# mapleCUx_large_067.net
KiCad netlist of a schematic drawn in EAGLE
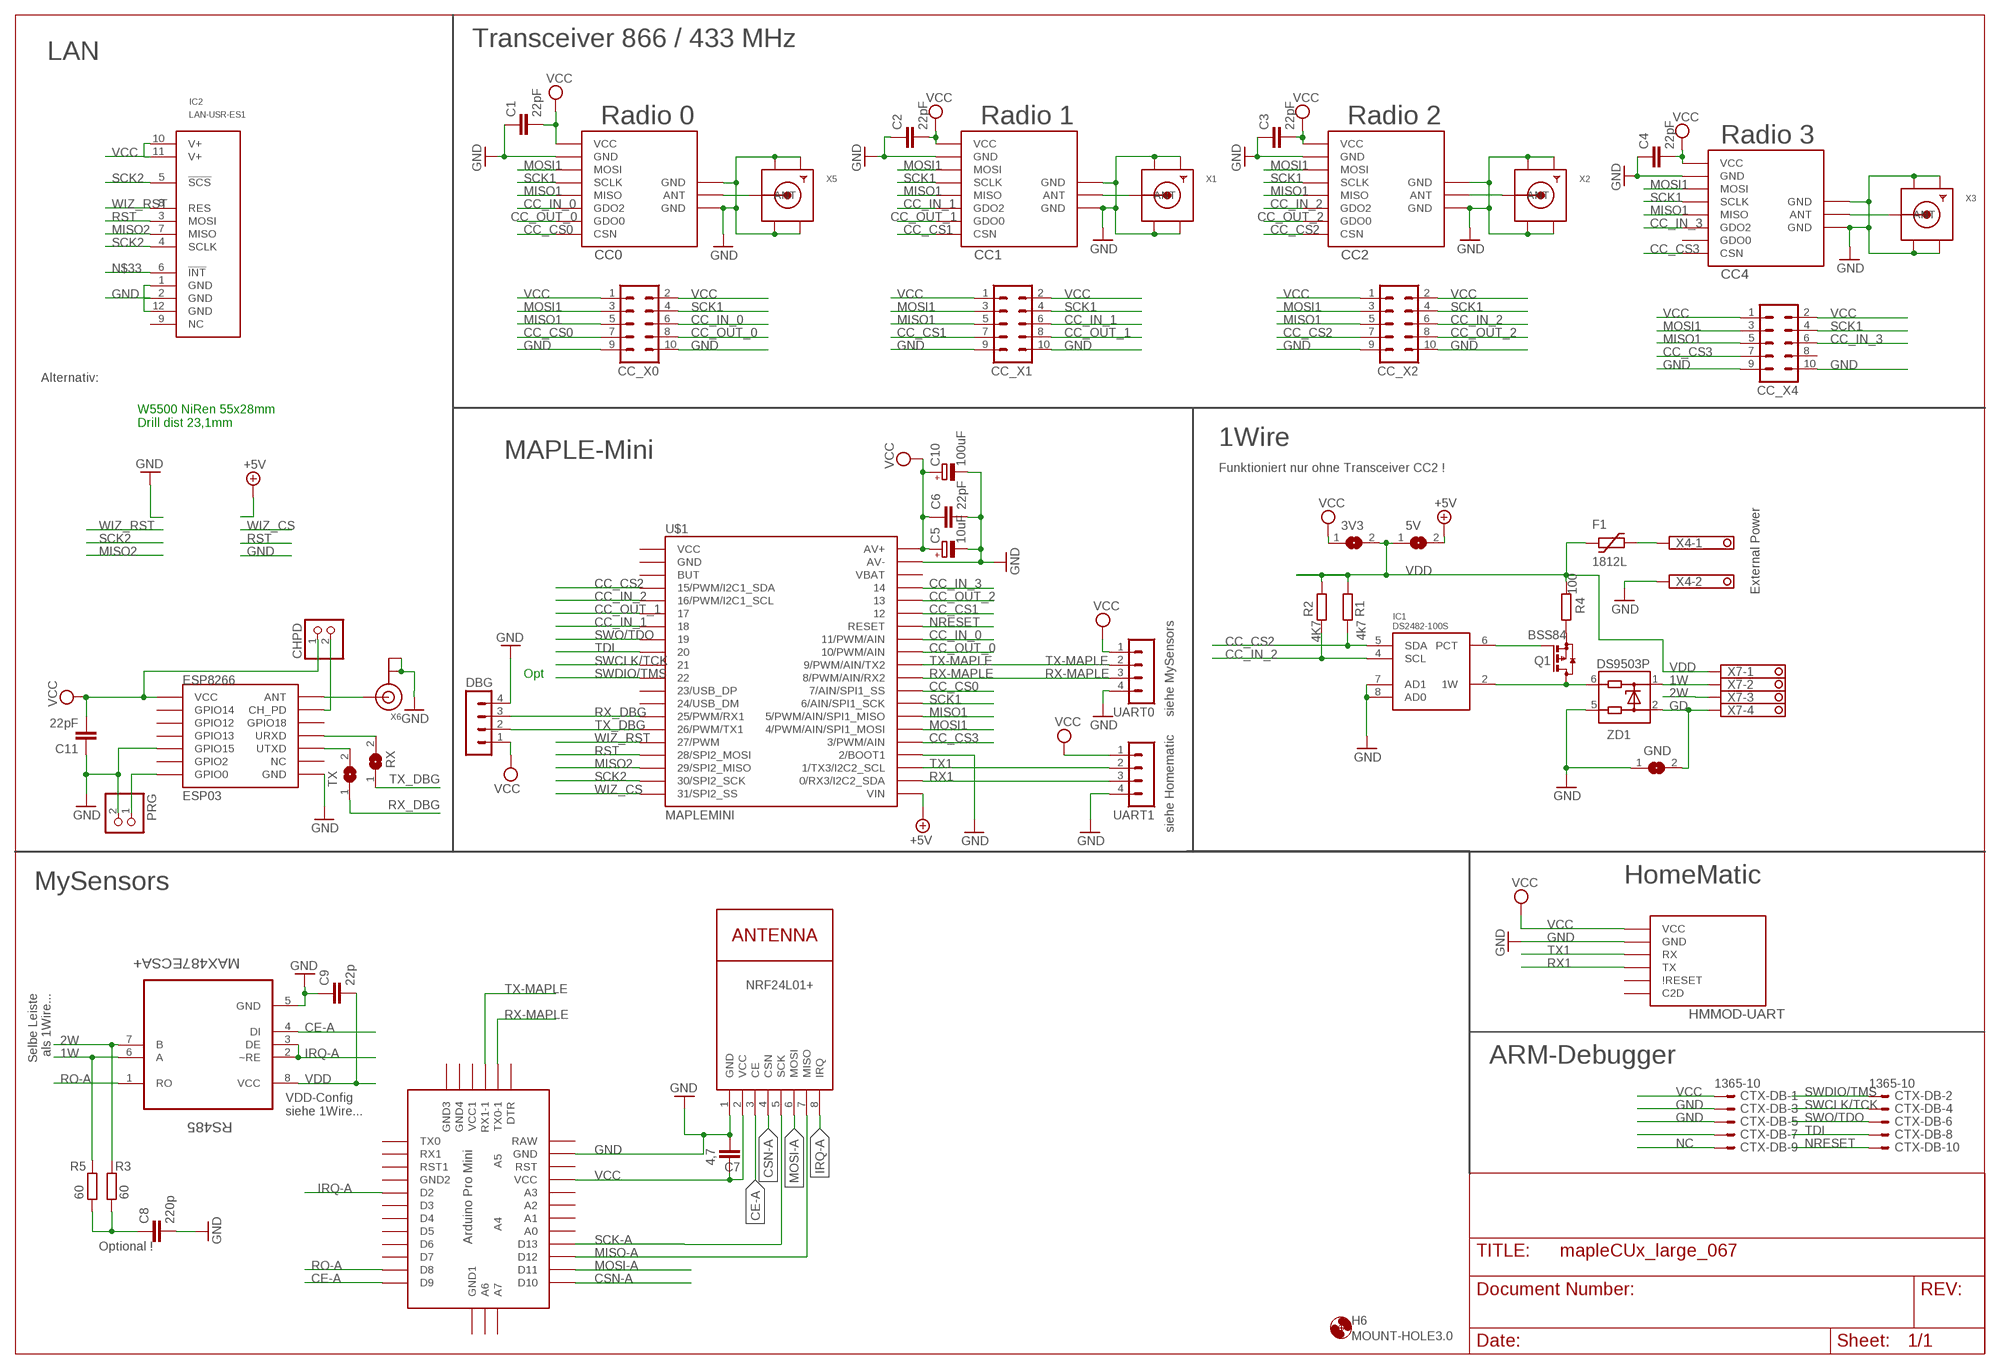
[diagram p0: schematic, sheet 1]

(export (version "E")
  (design (tool "Eeschema 10.0.6"))
  (components
    (comp (ref "3V3") (value "SJ") (footprint "eagle-import:SJ") (libsource (lib "eagle-import") (part "SJ")))
    (comp (ref "5V") (value "SJ") (footprint "eagle-import:SJ") (libsource (lib "eagle-import") (part "SJ")))
    (comp (ref "C1")
      (value "22pF")
      (footprint "eagle-import:C0805")
      (libsource (lib "eagle-import") (part "C-EUC0805"))
    )
    (comp (ref "C2")
      (value "22pF")
      (footprint "eagle-import:C0805")
      (libsource (lib "eagle-import") (part "C-EUC0805"))
    )
    (comp (ref "C3")
      (value "22pF")
      (footprint "eagle-import:C0805")
      (libsource (lib "eagle-import") (part "C-EUC0805"))
    )
    (comp (ref "C4")
      (value "22pF")
      (footprint "eagle-import:C0805")
      (libsource (lib "eagle-import") (part "C-EUC0805"))
    )
    (comp (ref "C5")
      (value "10uF")
      (footprint "eagle-import:R_2012-12W")
      (libsource (lib "eagle-import") (part "CPOL-EUR/2012-12W"))
    )
    (comp (ref "C6")
      (value "22pF")
      (footprint "eagle-import:C0805")
      (libsource (lib "eagle-import") (part "C-EUC0805"))
    )
    (comp (ref "C7")
      (value "4,7")
      (footprint "eagle-import:C1210")
      (libsource (lib "eagle-import") (part "C-EUC1210"))
    )
    (comp (ref "C8")
      (value "220p")
      (footprint "eagle-import:C0805")
      (libsource (lib "eagle-import") (part "C-EUC0805"))
    )
    (comp (ref "C9")
      (value "22p")
      (footprint "eagle-import:C0805")
      (libsource (lib "eagle-import") (part "C-EUC0805"))
    )
    (comp (ref "C10")
      (value "100uF")
      (footprint "eagle-import:E5-8,5")
      (libsource (lib "eagle-import") (part "CPOL-EUE5-8.5"))
    )
    (comp (ref "C11")
      (value "22pF")
      (footprint "eagle-import:C0805")
      (libsource (lib "eagle-import") (part "C-EUC0805"))
    )
    (comp (ref "CC0")
      (value "CC1101")
      (footprint "eagle-import:CC1101_MODULE1_SMD")
      (libsource (lib "eagle-import") (part "CC1101_MODULE1SMD"))
    )
    (comp (ref "CC1")
      (value "CC1101_MODULE1SMD")
      (footprint "eagle-import:CC1101_MODULE1_SMD")
      (libsource (lib "eagle-import") (part "CC1101_MODULE1SMD"))
    )
    (comp (ref "CC2")
      (value "CC1101_MODULE1SMD")
      (footprint "eagle-import:CC1101_MODULE1_SMD")
      (libsource (lib "eagle-import") (part "CC1101_MODULE1SMD"))
    )
    (comp (ref "CC4")
      (value "CC1101_MODULE1SMD")
      (footprint "eagle-import:CC1101_MODULE1_SMD")
      (libsource (lib "eagle-import") (part "CC1101_MODULE1SMD"))
    )
    (comp (ref "CC_X0")
      (value "MA05-2")
      (footprint "eagle-import:MA05-2")
      (libsource (lib "eagle-import") (part "MA05-2"))
    )
    (comp (ref "CC_X1")
      (value "MA05-2")
      (footprint "eagle-import:MA05-2")
      (libsource (lib "eagle-import") (part "MA05-2"))
    )
    (comp (ref "CC_X2")
      (value "MA05-2")
      (footprint "eagle-import:MA05-2")
      (libsource (lib "eagle-import") (part "MA05-2"))
    )
    (comp (ref "CC_X4")
      (value "MA05-2")
      (footprint "eagle-import:MA05-2")
      (libsource (lib "eagle-import") (part "MA05-2"))
    )
    (comp (ref "CHPD")
      (value "PINHD-1X2")
      (footprint "eagle-import:1X02")
      (libsource (lib "eagle-import") (part "PINHD-1X2"))
    )
    (comp (ref "CTX-DB")
      (value "1365-10")
      (footprint "eagle-import:1365-10")
      (libsource (lib "eagle-import") (part "1365-10"))
    )
    (comp (ref "DBG")
      (value "MA04-1")
      (footprint "eagle-import:MA04-1")
      (libsource (lib "eagle-import") (part "MA04-1"))
    )
    (comp (ref "ESP8266")
      (value "ESP03")
      (footprint "eagle-import:ESP03")
      (libsource (lib "eagle-import") (part "ESP03"))
    )
    (comp (ref "F1")
      (value "1812L")
      (footprint "eagle-import:1812L")
      (libsource (lib "eagle-import") (part "1812L"))
    )
    (comp (ref "GND") (value "SJ") (footprint "eagle-import:SJ") (libsource (lib "eagle-import") (part "SJ")))
    (comp (ref "H6")
      (value "MOUNT-HOLE3.0")
      (footprint "eagle-import:3,0")
      (libsource (lib "eagle-import") (part "MOUNT-HOLE3.0"))
    )
    (comp (ref "HMMOD-UART")
      (value "HM-MOD-UARTDIL")
      (footprint "eagle-import:HM-MOD-UART-DIL")
      (libsource (lib "eagle-import") (part "HM-MOD-UARTDIL"))
    )
    (comp (ref "IC1")
      (value "DS2482-100S")
      (footprint "eagle-import:SO08")
      (libsource (lib "eagle-import") (part "DS2482-100S"))
    )
    (comp (ref "IC2")
      (value "LAN-USR-ES1")
      (footprint "eagle-import:USR-ES1")
      (libsource (lib "eagle-import") (part "LAN-USR-ES1"))
    )
    (comp (ref "NRF24L01+")
      (value "NRF24L01+")
      (footprint "eagle-import:WIRELESS-NRF24L01")
      (libsource (lib "eagle-import") (part "WIRELESS-NRF24L01"))
    )
    (comp (ref "PRG")
      (value "PINHD-1X2")
      (footprint "eagle-import:1X02")
      (libsource (lib "eagle-import") (part "PINHD-1X2"))
    )
    (comp (ref "Q1")
      (value "BSS84")
      (footprint "eagle-import:SOT23")
      (libsource (lib "eagle-import") (part "BSS84"))
    )
    (comp (ref "R1")
      (value "4k7")
      (footprint "eagle-import:R0805")
      (libsource (lib "eagle-import") (part "R-EU_R0805"))
    )
    (comp (ref "R2")
      (value "4K7")
      (footprint "eagle-import:R0805")
      (libsource (lib "eagle-import") (part "R-EU_R0805"))
    )
    (comp (ref "R3")
      (value "60")
      (footprint "eagle-import:R0805")
      (libsource (lib "eagle-import") (part "R-EU_R0805"))
    )
    (comp (ref "R4")
      (value "100")
      (footprint "eagle-import:R0805")
      (libsource (lib "eagle-import") (part "R-EU_R0805"))
    )
    (comp (ref "R5")
      (value "60")
      (footprint "eagle-import:R0805")
      (libsource (lib "eagle-import") (part "R-EU_R0805"))
    )
    (comp (ref "RS485")
      (value "MAX487ECSA+")
      (footprint "eagle-import:SOIC127P600X175-8N")
      (libsource (lib "eagle-import") (part "MAX487ECSA+"))
    )
    (comp (ref "RX") (value "SJ") (footprint "eagle-import:SJ") (libsource (lib "eagle-import") (part "SJ")))
    (comp (ref "TX") (value "SJ") (footprint "eagle-import:SJ") (libsource (lib "eagle-import") (part "SJ")))
    (comp (ref "U$1")
      (value "MAPLEMINI")
      (footprint "eagle-import:20-DIP")
      (libsource (lib "eagle-import") (part "MAPLEMINI"))
    )
    (comp (ref "U$2")
      (value "ABK-PRO-MINI")
      (footprint "eagle-import:ABK-PRO-MINI")
      (libsource (lib "eagle-import") (part "ABK-PRO-MINI"))
    )
    (comp (ref "UART0")
      (value "MA04-1")
      (footprint "eagle-import:MA04-1")
      (libsource (lib "eagle-import") (part "MA04-1"))
    )
    (comp (ref "UART1")
      (value "MA04-1")
      (footprint "eagle-import:MA04-1")
      (libsource (lib "eagle-import") (part "MA04-1"))
    )
    (comp (ref "X1")
      (value "SMACONNECTOR_EDGE_UFL")
      (footprint "eagle-import:SMA_EDGELAUNCH_UFL")
      (libsource (lib "eagle-import") (part "SMACONNECTOR_EDGE_UFL"))
    )
    (comp (ref "X2")
      (value "SMACONNECTOR_EDGE_UFL")
      (footprint "eagle-import:SMA_EDGELAUNCH_UFL")
      (libsource (lib "eagle-import") (part "SMACONNECTOR_EDGE_UFL"))
    )
    (comp (ref "X3")
      (value "SMACONNECTOR_EDGE_UFL")
      (footprint "eagle-import:SMA_EDGELAUNCH_UFL")
      (libsource (lib "eagle-import") (part "SMACONNECTOR_EDGE_UFL"))
    )
    (comp (ref "X4")
      (value "1751248")
      (footprint "eagle-import:1751248")
      (libsource (lib "eagle-import") (part "1751248"))
    )
    (comp (ref "X5")
      (value "SMACONNECTOR_EDGE_UFL")
      (footprint "eagle-import:SMA_EDGELAUNCH_UFL")
      (libsource (lib "eagle-import") (part "SMACONNECTOR_EDGE_UFL"))
    )
    (comp (ref "X6")
      (value "ANTENNA_U.FL")
      (footprint "eagle-import:U.FL")
      (libsource (lib "eagle-import") (part "ANTENNA_U.FL"))
    )
    (comp (ref "X7")
      (value "1751264")
      (footprint "eagle-import:1751264")
      (libsource (lib "eagle-import") (part "1751264"))
    )
    (comp (ref "ZD1")
      (value "DS9503P")
      (footprint "eagle-import:TSOC6")
      (libsource (lib "eagle-import") (part "DS9503P"))
    )
  )
  (nets
    (net (code "1") (name "+5V") (class "Default")
      (node (ref "5V") (pin "2") (pinfunction "2_2") (pintype "passive"))
      (node (ref "U$1") (pin "21") (pinfunction "VIN_21") (pintype "bidirectional"))
    )
    (net (code "2") (name "/1W") (class "Default")
      (node (ref "R5") (pin "2") (pinfunction "2_2") (pintype "passive"))
      (node (ref "RS485") (pin "6") (pinfunction "A_6") (pintype "bidirectional"))
      (node (ref "X7") (pin "2") (pinfunction "K_2") (pintype "passive"))
      (node (ref "ZD1") (pin "1") (pinfunction "P$1_1") (pintype "passive"))
    )
    (net (code "3") (name "/2W") (class "Default")
      (node (ref "R3") (pin "2") (pinfunction "2_2") (pintype "passive"))
      (node (ref "RS485") (pin "7") (pinfunction "B_7") (pintype "bidirectional"))
      (node (ref "X7") (pin "3") (pinfunction "K_3") (pintype "passive"))
    )
    (net (code "4") (name "/CC_CS0") (class "Default")
      (node (ref "CC0") (pin "CSN") (pinfunction "CSN_CSN") (pintype "bidirectional"))
      (node (ref "CC_X0") (pin "7") (pinfunction "7_7") (pintype "passive"))
      (node (ref "U$1") (pin "29") (pinfunction "7/AIN/SPI1_SS_29") (pintype "bidirectional"))
    )
    (net (code "5") (name "/CC_CS1") (class "Default")
      (node (ref "CC1") (pin "CSN") (pinfunction "CSN_CSN") (pintype "bidirectional"))
      (node (ref "CC_X1") (pin "7") (pinfunction "7_7") (pintype "passive"))
      (node (ref "U$1") (pin "35") (pinfunction "12_35") (pintype "bidirectional"))
    )
    (net (code "6") (name "/CC_CS2") (class "Default")
      (node (ref "CC2") (pin "CSN") (pinfunction "CSN_CSN") (pintype "bidirectional"))
      (node (ref "CC_X2") (pin "7") (pinfunction "7_7") (pintype "passive"))
      (node (ref "IC1") (pin "5") (pinfunction "SDA_5") (pintype "bidirectional"))
      (node (ref "R1") (pin "2") (pinfunction "2_2") (pintype "passive"))
      (node (ref "U$1") (pin "4") (pinfunction "15/PWM/I2C1_SDA_4") (pintype "bidirectional"))
    )
    (net (code "7") (name "/CC_CS3") (class "Default")
      (node (ref "CC4") (pin "CSN") (pinfunction "CSN_CSN") (pintype "bidirectional"))
      (node (ref "CC_X4") (pin "7") (pinfunction "7_7") (pintype "passive"))
      (node (ref "U$1") (pin "25") (pinfunction "3/PWM/AIN_25") (pintype "bidirectional"))
    )
    (net (code "8") (name "/CC_IN_0") (class "Default")
      (node (ref "CC0") (pin "GDO2") (pinfunction "GDO2_GDO2") (pintype "bidirectional"))
      (node (ref "CC_X0") (pin "6") (pinfunction "6_6") (pintype "passive"))
      (node (ref "U$1") (pin "33") (pinfunction "11/PWM/AIN_33") (pintype "bidirectional"))
    )
    (net (code "9") (name "/CC_IN_1") (class "Default")
      (node (ref "CC1") (pin "GDO2") (pinfunction "GDO2_GDO2") (pintype "bidirectional"))
      (node (ref "CC_X1") (pin "6") (pinfunction "6_6") (pintype "passive"))
      (node (ref "U$1") (pin "7") (pinfunction "18_7") (pintype "bidirectional"))
    )
    (net (code "10") (name "/CC_IN_2") (class "Default")
      (node (ref "CC2") (pin "GDO2") (pinfunction "GDO2_GDO2") (pintype "bidirectional"))
      (node (ref "CC_X2") (pin "6") (pinfunction "6_6") (pintype "passive"))
      (node (ref "IC1") (pin "4") (pinfunction "SCL_4") (pintype "input"))
      (node (ref "R2") (pin "2") (pinfunction "2_2") (pintype "passive"))
      (node (ref "U$1") (pin "5") (pinfunction "16/PWM/I2C1_SCL_5") (pintype "bidirectional"))
    )
    (net (code "11") (name "/CC_IN_3") (class "Default")
      (node (ref "CC4") (pin "GDO2") (pinfunction "GDO2_GDO2") (pintype "bidirectional"))
      (node (ref "CC_X4") (pin "6") (pinfunction "6_6") (pintype "passive"))
      (node (ref "U$1") (pin "37") (pinfunction "14_37") (pintype "bidirectional"))
    )
    (net (code "12") (name "/CC_OUT_0") (class "Default")
      (node (ref "CC0") (pin "GDO0") (pinfunction "GDO0_GDO0") (pintype "bidirectional"))
      (node (ref "CC_X0") (pin "8") (pinfunction "8_8") (pintype "passive"))
      (node (ref "U$1") (pin "32") (pinfunction "10/PWM/AIN_32") (pintype "bidirectional"))
    )
    (net (code "13") (name "/CC_OUT_1") (class "Default")
      (node (ref "CC1") (pin "GDO0") (pinfunction "GDO0_GDO0") (pintype "bidirectional"))
      (node (ref "CC_X1") (pin "8") (pinfunction "8_8") (pintype "passive"))
      (node (ref "U$1") (pin "6") (pinfunction "17_6") (pintype "bidirectional"))
    )
    (net (code "14") (name "/CC_OUT_2") (class "Default")
      (node (ref "CC2") (pin "GDO0") (pinfunction "GDO0_GDO0") (pintype "bidirectional"))
      (node (ref "CC_X2") (pin "8") (pinfunction "8_8") (pintype "passive"))
      (node (ref "U$1") (pin "36") (pinfunction "13_36") (pintype "bidirectional"))
    )
    (net (code "15") (name "/GD") (class "Default")
      (node (ref "GND") (pin "2") (pinfunction "2_2") (pintype "passive"))
      (node (ref "X7") (pin "4") (pinfunction "K_4") (pintype "passive"))
      (node (ref "ZD1") (pin "2") (pinfunction "P$2_2") (pintype "passive"))
    )
    (net (code "16") (name "/MISO-A") (class "Default")
      (node (ref "NRF24L01+") (pin "7") (pinfunction "MISO_7") (pintype "bidirectional"))
      (node (ref "U$2") (pin "D12") (pinfunction "D12_D12") (pintype "bidirectional"))
    )
    (net (code "17") (name "/MISO1") (class "Default")
      (node (ref "CC0") (pin "MISO") (pinfunction "MISO_MISO") (pintype "bidirectional"))
      (node (ref "CC1") (pin "MISO") (pinfunction "MISO_MISO") (pintype "bidirectional"))
      (node (ref "CC2") (pin "MISO") (pinfunction "MISO_MISO") (pintype "bidirectional"))
      (node (ref "CC4") (pin "MISO") (pinfunction "MISO_MISO") (pintype "bidirectional"))
      (node (ref "CC_X0") (pin "5") (pinfunction "5_5") (pintype "passive"))
      (node (ref "CC_X1") (pin "5") (pinfunction "5_5") (pintype "passive"))
      (node (ref "CC_X2") (pin "5") (pinfunction "5_5") (pintype "passive"))
      (node (ref "CC_X4") (pin "5") (pinfunction "5_5") (pintype "passive"))
      (node (ref "U$1") (pin "27") (pinfunction "5/PWM/AIN/SPI1_MISO_27") (pintype "bidirectional"))
    )
    (net (code "18") (name "/MISO2") (class "Default")
      (node (ref "IC2") (pin "7") (pinfunction "MISO_7") (pintype "bidirectional"))
      (node (ref "U$1") (pin "18") (pinfunction "29/SPI2_MISO_18") (pintype "bidirectional"))
    )
    (net (code "19") (name "/MOSI1") (class "Default")
      (node (ref "CC0") (pin "MOSI") (pinfunction "MOSI_MOSI") (pintype "bidirectional"))
      (node (ref "CC1") (pin "MOSI") (pinfunction "MOSI_MOSI") (pintype "bidirectional"))
      (node (ref "CC2") (pin "MOSI") (pinfunction "MOSI_MOSI") (pintype "bidirectional"))
      (node (ref "CC4") (pin "MOSI") (pinfunction "MOSI_MOSI") (pintype "bidirectional"))
      (node (ref "CC_X0") (pin "3") (pinfunction "3_3") (pintype "passive"))
      (node (ref "CC_X1") (pin "3") (pinfunction "3_3") (pintype "passive"))
      (node (ref "CC_X2") (pin "3") (pinfunction "3_3") (pintype "passive"))
      (node (ref "CC_X4") (pin "3") (pinfunction "3_3") (pintype "passive"))
      (node (ref "U$1") (pin "26") (pinfunction "4/PWM/AIN/SPI1_MOSI_26") (pintype "bidirectional"))
    )
    (net (code "20") (name "/N$33") (class "Default")
      (node (ref "IC2") (pin "6") (pinfunction "~{INT}_6") (pintype "output"))
    )
    (net (code "21") (name "/NC") (class "Default")
      (node (ref "CTX-DB") (pin "9") (pinfunction "S_9") (pintype "passive"))
    )
    (net (code "22") (name "/NRESET") (class "Default")
      (node (ref "CTX-DB") (pin "10") (pinfunction "S_10") (pintype "passive"))
      (node (ref "U$1") (pin "34") (pinfunction "RESET_34") (pintype "bidirectional"))
    )
    (net (code "23") (name "/RO-A") (class "Default")
      (node (ref "RS485") (pin "1") (pinfunction "RO_1") (pintype "output"))
      (node (ref "U$2") (pin "D8") (pinfunction "D8_D8") (pintype "bidirectional"))
    )
    (net (code "24") (name "/RST") (class "Default")
      (node (ref "IC2") (pin "3") (pinfunction "MOSI_3") (pintype "bidirectional"))
      (node (ref "U$1") (pin "17") (pinfunction "28/SPI2_MOSI_17") (pintype "bidirectional"))
    )
    (net (code "25") (name "/RX-MAPLE") (class "Default")
      (node (ref "U$1") (pin "30") (pinfunction "8/PWM/AIN/RX2_30") (pintype "bidirectional"))
      (node (ref "U$2") (pin "TX0-1") (pinfunction "TX0-1_TX0-1") (pintype "bidirectional"))
      (node (ref "UART0") (pin "3") (pinfunction "3_3") (pintype "passive"))
    )
    (net (code "26") (name "/RX1") (class "Default")
      (node (ref "HMMOD-UART") (pin "5") (pinfunction "TX_5") (pintype "bidirectional"))
      (node (ref "U$1") (pin "22") (pinfunction "0/RX3/I2C2_SDA_22") (pintype "bidirectional"))
      (node (ref "UART1") (pin "3") (pinfunction "3_3") (pintype "passive"))
    )
    (net (code "27") (name "/RX_DBG") (class "Default")
      (node (ref "DBG") (pin "3") (pinfunction "3_3") (pintype "passive"))
      (node (ref "TX") (pin "1") (pinfunction "1_1") (pintype "passive"))
      (node (ref "U$1") (pin "14") (pinfunction "25/PWM/RX1_14") (pintype "bidirectional"))
    )
    (net (code "28") (name "/SCK-A") (class "Default")
      (node (ref "NRF24L01+") (pin "5") (pinfunction "SCK_5") (pintype "bidirectional"))
      (node (ref "U$2") (pin "D13") (pinfunction "D13_D13") (pintype "bidirectional"))
    )
    (net (code "29") (name "/SCK1") (class "Default")
      (node (ref "CC0") (pin "SCLK") (pinfunction "SCLK_SCLK") (pintype "bidirectional"))
      (node (ref "CC1") (pin "SCLK") (pinfunction "SCLK_SCLK") (pintype "bidirectional"))
      (node (ref "CC2") (pin "SCLK") (pinfunction "SCLK_SCLK") (pintype "bidirectional"))
      (node (ref "CC4") (pin "SCLK") (pinfunction "SCLK_SCLK") (pintype "bidirectional"))
      (node (ref "CC_X0") (pin "4") (pinfunction "4_4") (pintype "passive"))
      (node (ref "CC_X1") (pin "4") (pinfunction "4_4") (pintype "passive"))
      (node (ref "CC_X2") (pin "4") (pinfunction "4_4") (pintype "passive"))
      (node (ref "CC_X4") (pin "4") (pinfunction "4_4") (pintype "passive"))
      (node (ref "U$1") (pin "28") (pinfunction "6/AIN/SPI1_SCK_28") (pintype "bidirectional"))
    )
    (net (code "30") (name "/SCK2") (class "Default")
      (node (ref "IC2") (pin "4") (pinfunction "SCLK_4") (pintype "input"))
      (node (ref "IC2") (pin "5") (pinfunction "~{SCS}_5") (pintype "input"))
      (node (ref "U$1") (pin "19") (pinfunction "30/SPI2_SCK_19") (pintype "bidirectional"))
    )
    (net (code "31") (name "/SWCLK{slash}TCK") (class "Default")
      (node (ref "CTX-DB") (pin "4") (pinfunction "S_4") (pintype "passive"))
      (node (ref "U$1") (pin "10") (pinfunction "21_10") (pintype "bidirectional"))
    )
    (net (code "32") (name "/SWDIO{slash}TMS") (class "Default")
      (node (ref "CTX-DB") (pin "2") (pinfunction "S_2") (pintype "passive"))
      (node (ref "U$1") (pin "11") (pinfunction "22_11") (pintype "bidirectional"))
    )
    (net (code "33") (name "/SWO{slash}TDO") (class "Default")
      (node (ref "CTX-DB") (pin "6") (pinfunction "S_6") (pintype "passive"))
      (node (ref "U$1") (pin "8") (pinfunction "19_8") (pintype "bidirectional"))
    )
    (net (code "34") (name "/TDI") (class "Default")
      (node (ref "CTX-DB") (pin "8") (pinfunction "S_8") (pintype "passive"))
      (node (ref "U$1") (pin "9") (pinfunction "20_9") (pintype "bidirectional"))
    )
    (net (code "35") (name "/TX-MAPLE") (class "Default")
      (node (ref "U$1") (pin "31") (pinfunction "9/PWM/AIN/TX2_31") (pintype "bidirectional"))
      (node (ref "U$2") (pin "RX1-1") (pinfunction "RX1-1_RX1-1") (pintype "bidirectional"))
      (node (ref "UART0") (pin "2") (pinfunction "2_2") (pintype "passive"))
    )
    (net (code "36") (name "/TX1") (class "Default")
      (node (ref "HMMOD-UART") (pin "6") (pinfunction "RX_6") (pintype "bidirectional"))
      (node (ref "U$1") (pin "23") (pinfunction "1/TX3/I2C2_SCL_23") (pintype "bidirectional"))
      (node (ref "UART1") (pin "2") (pinfunction "2_2") (pintype "passive"))
    )
    (net (code "37") (name "/TX_DBG") (class "Default")
      (node (ref "DBG") (pin "2") (pinfunction "2_2") (pintype "passive"))
      (node (ref "RX") (pin "1") (pinfunction "1_1") (pintype "passive"))
      (node (ref "U$1") (pin "15") (pinfunction "26/PWM/TX1_15") (pintype "bidirectional"))
    )
    (net (code "38") (name "/VDD") (class "Default")
      (node (ref "3V3") (pin "2") (pinfunction "2_2") (pintype "passive"))
      (node (ref "5V") (pin "1") (pinfunction "1_1") (pintype "passive"))
      (node (ref "C9") (pin "2") (pinfunction "2_2") (pintype "passive"))
      (node (ref "F1") (pin "P$1") (pinfunction "1_P$1") (pintype "passive"))
      (node (ref "R1") (pin "1") (pinfunction "1_1") (pintype "passive"))
      (node (ref "R2") (pin "1") (pinfunction "1_1") (pintype "passive"))
      (node (ref "R4") (pin "2") (pinfunction "2_2") (pintype "passive"))
      (node (ref "RS485") (pin "8") (pinfunction "VCC_8") (pintype "power_in"))
      (node (ref "X7") (pin "1") (pinfunction "K_1") (pintype "passive"))
    )
    (net (code "39") (name "/WIZ_CS") (class "Default")
      (node (ref "U$1") (pin "20") (pinfunction "31/SPI2_SS_20") (pintype "bidirectional"))
    )
    (net (code "40") (name "/WIZ_RST") (class "Default")
      (node (ref "IC2") (pin "8") (pinfunction "RES_8") (pintype "input"))
      (node (ref "U$1") (pin "16") (pinfunction "27/PWM_16") (pintype "bidirectional"))
    )
    (net (code "41") (name "CE-A") (class "Default")
      (node (ref "NRF24L01+") (pin "3") (pinfunction "CE_3") (pintype "bidirectional"))
      (node (ref "RS485") (pin "4") (pinfunction "DI_4") (pintype "input"))
      (node (ref "U$2") (pin "D9") (pinfunction "D9_D9") (pintype "bidirectional"))
    )
    (net (code "42") (name "CSN-A") (class "Default")
      (node (ref "NRF24L01+") (pin "4") (pinfunction "CSN_4") (pintype "bidirectional"))
      (node (ref "U$2") (pin "D10") (pinfunction "D10_D10") (pintype "bidirectional"))
    )
    (net (code "43") (name "GND") (class "Default")
      (node (ref "C1") (pin "1") (pinfunction "1_1") (pintype "passive"))
      (node (ref "C10") (pin "-") (pinfunction "-_-") (pintype "passive"))
      (node (ref "C11") (pin "1") (pinfunction "1_1") (pintype "passive"))
      (node (ref "C2") (pin "1") (pinfunction "1_1") (pintype "passive"))
      (node (ref "C3") (pin "1") (pinfunction "1_1") (pintype "passive"))
      (node (ref "C4") (pin "1") (pinfunction "1_1") (pintype "passive"))
      (node (ref "C5") (pin "-") (pinfunction "-_-") (pintype "passive"))
      (node (ref "C6") (pin "2") (pinfunction "2_2") (pintype "passive"))
      (node (ref "C7") (pin "1") (pinfunction "1_1") (pintype "passive"))
      (node (ref "C8") (pin "2") (pinfunction "2_2") (pintype "passive"))
      (node (ref "C9") (pin "1") (pinfunction "1_1") (pintype "passive"))
      (node (ref "CC0") (pin "GND@0") (pinfunction "GND_GND@0") (pintype "power_in"))
      (node (ref "CC0") (pin "GND@1") (pinfunction "GND_GND@1") (pintype "power_in"))
      (node (ref "CC0") (pin "GND@2") (pinfunction "GND_GND@2") (pintype "power_in"))
      (node (ref "CC1") (pin "GND@0") (pinfunction "GND_GND@0") (pintype "power_in"))
      (node (ref "CC1") (pin "GND@1") (pinfunction "GND_GND@1") (pintype "power_in"))
      (node (ref "CC1") (pin "GND@2") (pinfunction "GND_GND@2") (pintype "power_in"))
      (node (ref "CC2") (pin "GND@0") (pinfunction "GND_GND@0") (pintype "power_in"))
      (node (ref "CC2") (pin "GND@1") (pinfunction "GND_GND@1") (pintype "power_in"))
      (node (ref "CC2") (pin "GND@2") (pinfunction "GND_GND@2") (pintype "power_in"))
      (node (ref "CC4") (pin "GND@0") (pinfunction "GND_GND@0") (pintype "power_in"))
      (node (ref "CC4") (pin "GND@1") (pinfunction "GND_GND@1") (pintype "power_in"))
      (node (ref "CC4") (pin "GND@2") (pinfunction "GND_GND@2") (pintype "power_in"))
      (node (ref "CC_X0") (pin "10") (pinfunction "10_10") (pintype "passive"))
      (node (ref "CC_X0") (pin "9") (pinfunction "9_9") (pintype "passive"))
      (node (ref "CC_X1") (pin "10") (pinfunction "10_10") (pintype "passive"))
      (node (ref "CC_X1") (pin "9") (pinfunction "9_9") (pintype "passive"))
      (node (ref "CC_X2") (pin "10") (pinfunction "10_10") (pintype "passive"))
      (node (ref "CC_X2") (pin "9") (pinfunction "9_9") (pintype "passive"))
      (node (ref "CC_X4") (pin "10") (pinfunction "10_10") (pintype "passive"))
      (node (ref "CC_X4") (pin "9") (pinfunction "9_9") (pintype "passive"))
      (node (ref "CTX-DB") (pin "3") (pinfunction "S_3") (pintype "passive"))
      (node (ref "CTX-DB") (pin "5") (pinfunction "S_5") (pintype "passive"))
      (node (ref "DBG") (pin "4") (pinfunction "4_4") (pintype "passive"))
      (node (ref "ESP8266") (pin "GND") (pinfunction "GND_GND") (pintype "bidirectional"))
      (node (ref "ESP8266") (pin "GPIO15") (pinfunction "GPIO15_GPIO15") (pintype "bidirectional"))
      (node (ref "GND") (pin "1") (pinfunction "1_1") (pintype "passive"))
      (node (ref "HMMOD-UART") (pin "2") (pinfunction "GND_2") (pintype "power_in"))
      (node (ref "IC1") (pin "7") (pinfunction "AD1_7") (pintype "input"))
      (node (ref "IC1") (pin "8") (pinfunction "AD0_8") (pintype "input"))
      (node (ref "IC2") (pin "1") (pinfunction "GND_1") (pintype "power_in"))
      (node (ref "IC2") (pin "12") (pinfunction "GND_12") (pintype "power_in"))
      (node (ref "IC2") (pin "2") (pinfunction "GND_2") (pintype "power_in"))
      (node (ref "NRF24L01+") (pin "1") (pinfunction "GND_1") (pintype "power_in"))
      (node (ref "PRG") (pin "2") (pinfunction "2_2") (pintype "passive"))
      (node (ref "RS485") (pin "5") (pinfunction "GND_5") (pintype "passive"))
      (node (ref "U$1") (pin "24") (pinfunction "2/BOOT1_24") (pintype "bidirectional"))
      (node (ref "U$1") (pin "39") (pinfunction "AV-_39") (pintype "bidirectional"))
      (node (ref "U$2") (pin "GND") (pinfunction "GND_GND") (pintype "bidirectional"))
      (node (ref "UART0") (pin "4") (pinfunction "4_4") (pintype "passive"))
      (node (ref "UART1") (pin "4") (pinfunction "4_4") (pintype "passive"))
      (node (ref "X1") (pin "GND@1") (pinfunction "GND1_GND@1") (pintype "power_in"))
      (node (ref "X1") (pin "GND@2") (pinfunction "GND2_GND@2") (pintype "power_in"))
      (node (ref "X1") (pin "GND@3") (pinfunction "GND3_GND@3") (pintype "power_in"))
      (node (ref "X1") (pin "GND@4") (pinfunction "GND4_GND@4") (pintype "power_in"))
      (node (ref "X2") (pin "GND@1") (pinfunction "GND1_GND@1") (pintype "power_in"))
      (node (ref "X2") (pin "GND@2") (pinfunction "GND2_GND@2") (pintype "power_in"))
      (node (ref "X2") (pin "GND@3") (pinfunction "GND3_GND@3") (pintype "power_in"))
      (node (ref "X2") (pin "GND@4") (pinfunction "GND4_GND@4") (pintype "power_in"))
      (node (ref "X3") (pin "GND@1") (pinfunction "GND1_GND@1") (pintype "power_in"))
      (node (ref "X3") (pin "GND@2") (pinfunction "GND2_GND@2") (pintype "power_in"))
      (node (ref "X3") (pin "GND@3") (pinfunction "GND3_GND@3") (pintype "power_in"))
      (node (ref "X3") (pin "GND@4") (pinfunction "GND4_GND@4") (pintype "power_in"))
      (node (ref "X4") (pin "2") (pinfunction "K_2") (pintype "passive"))
      (node (ref "X5") (pin "GND@1") (pinfunction "GND1_GND@1") (pintype "power_in"))
      (node (ref "X5") (pin "GND@2") (pinfunction "GND2_GND@2") (pintype "power_in"))
      (node (ref "X5") (pin "GND@3") (pinfunction "GND3_GND@3") (pintype "power_in"))
      (node (ref "X5") (pin "GND@4") (pinfunction "GND4_GND@4") (pintype "power_in"))
      (node (ref "X6") (pin "1") (pinfunction "GND_1") (pintype "passive"))
      (node (ref "X6") (pin "2") (pinfunction "GND_2") (pintype "passive"))
      (node (ref "ZD1") (pin "5") (pinfunction "P$3_5") (pintype "passive"))
    )
    (net (code "44") (name "IRQ-A") (class "Default")
      (node (ref "NRF24L01+") (pin "8") (pinfunction "IRQ_8") (pintype "bidirectional"))
      (node (ref "RS485") (pin "2") (pinfunction "~{RE}_2") (pintype "input"))
      (node (ref "RS485") (pin "3") (pinfunction "DE_3") (pintype "input"))
      (node (ref "U$2") (pin "D2") (pinfunction "D2_D2") (pintype "bidirectional"))
    )
    (net (code "45") (name "MOSI-A") (class "Default")
      (node (ref "NRF24L01+") (pin "6") (pinfunction "MOSI_6") (pintype "bidirectional"))
      (node (ref "U$2") (pin "D11") (pinfunction "D11_D11") (pintype "bidirectional"))
    )
    (net (code "46") (name "Net-(C8-Pad1)") (class "Default")
      (node (ref "C8") (pin "1") (pinfunction "1_1") (pintype "passive"))
      (node (ref "R3") (pin "1") (pinfunction "1_1") (pintype "passive"))
      (node (ref "R5") (pin "1") (pinfunction "1_1") (pintype "passive"))
    )
    (net (code "47") (name "Net-(CHPD-Pad2)") (class "Default")
      (node (ref "CHPD") (pin "2") (pinfunction "2_2") (pintype "passive"))
      (node (ref "ESP8266") (pin "CH_PD") (pinfunction "CH_PD_CH_PD") (pintype "bidirectional"))
    )
    (net (code "48") (name "Net-(ESP8266-PadGPIO0)") (class "Default")
      (node (ref "ESP8266") (pin "GPIO0") (pinfunction "GPIO0_GPIO0") (pintype "bidirectional"))
      (node (ref "PRG") (pin "1") (pinfunction "1_1") (pintype "passive"))
    )
    (net (code "49") (name "Net-(ESP8266-PadURXD)") (class "Default")
      (node (ref "ESP8266") (pin "URXD") (pinfunction "URXD_URXD") (pintype "bidirectional"))
      (node (ref "RX") (pin "2") (pinfunction "2_2") (pintype "passive"))
    )
    (net (code "50") (name "Net-(ESP8266-PadUTXD)") (class "Default")
      (node (ref "ESP8266") (pin "UTXD") (pinfunction "UTXD_UTXD") (pintype "bidirectional"))
      (node (ref "TX") (pin "2") (pinfunction "2_2") (pintype "passive"))
    )
    (net (code "51") (name "Net-(F1-2)") (class "Default")
      (node (ref "F1") (pin "P$2") (pinfunction "2_P$2") (pintype "passive"))
      (node (ref "X4") (pin "1") (pinfunction "K_1") (pintype "passive"))
    )
    (net (code "52") (name "Net-(IC1A-1W)") (class "Default")
      (node (ref "IC1") (pin "2") (pinfunction "1W_2") (pintype "open_collector"))
      (node (ref "Q1") (pin "3") (pinfunction "D_3") (pintype "passive"))
      (node (ref "ZD1") (pin "6") (pinfunction "P$4_6") (pintype "passive"))
    )
    (net (code "53") (name "Net-(IC1A-PCT)") (class "Default")
      (node (ref "IC1") (pin "6") (pinfunction "PCT_6") (pintype "output"))
      (node (ref "Q1") (pin "1") (pinfunction "G_1") (pintype "passive"))
    )
    (net (code "54") (name "Net-(Q1-S)") (class "Default")
      (node (ref "Q1") (pin "2") (pinfunction "S_2") (pintype "passive"))
      (node (ref "R4") (pin "1") (pinfunction "1_1") (pintype "passive"))
    )
    (net (code "55") (name "Net-(X1-ANT)") (class "Default")
      (node (ref "CC1") (pin "ANT") (pinfunction "ANT_ANT") (pintype "output"))
      (node (ref "X1") (pin "P") (pinfunction "ANT_P") (pintype "bidirectional"))
    )
    (net (code "56") (name "Net-(X2-ANT)") (class "Default")
      (node (ref "CC2") (pin "ANT") (pinfunction "ANT_ANT") (pintype "output"))
      (node (ref "X2") (pin "P") (pinfunction "ANT_P") (pintype "bidirectional"))
    )
    (net (code "57") (name "Net-(X3-ANT)") (class "Default")
      (node (ref "CC4") (pin "ANT") (pinfunction "ANT_ANT") (pintype "output"))
      (node (ref "X3") (pin "P") (pinfunction "ANT_P") (pintype "bidirectional"))
    )
    (net (code "58") (name "Net-(X5-ANT)") (class "Default")
      (node (ref "CC0") (pin "ANT") (pinfunction "ANT_ANT") (pintype "output"))
      (node (ref "X5") (pin "P") (pinfunction "ANT_P") (pintype "bidirectional"))
    )
    (net (code "59") (name "Net-(X6-SIGNAL)") (class "Default")
      (node (ref "ESP8266") (pin "ANT") (pinfunction "ANT_ANT") (pintype "bidirectional"))
      (node (ref "X6") (pin "3") (pinfunction "SIGNAL_3") (pintype "passive"))
    )
    (net (code "60") (name "VCC") (class "Default")
      (node (ref "3V3") (pin "1") (pinfunction "1_1") (pintype "passive"))
      (node (ref "C1") (pin "2") (pinfunction "2_2") (pintype "passive"))
      (node (ref "C10") (pin "+") (pinfunction "+_+") (pintype "passive"))
      (node (ref "C11") (pin "2") (pinfunction "2_2") (pintype "passive"))
      (node (ref "C2") (pin "2") (pinfunction "2_2") (pintype "passive"))
      (node (ref "C3") (pin "2") (pinfunction "2_2") (pintype "passive"))
      (node (ref "C4") (pin "2") (pinfunction "2_2") (pintype "passive"))
      (node (ref "C5") (pin "+") (pinfunction "+_+") (pintype "passive"))
      (node (ref "C6") (pin "1") (pinfunction "1_1") (pintype "passive"))
      (node (ref "C7") (pin "2") (pinfunction "2_2") (pintype "passive"))
      (node (ref "CC0") (pin "VCC") (pinfunction "VCC_VCC") (pintype "power_in"))
      (node (ref "CC1") (pin "VCC") (pinfunction "VCC_VCC") (pintype "power_in"))
      (node (ref "CC2") (pin "VCC") (pinfunction "VCC_VCC") (pintype "power_in"))
      (node (ref "CC4") (pin "VCC") (pinfunction "VCC_VCC") (pintype "power_in"))
      (node (ref "CC_X0") (pin "1") (pinfunction "1_1") (pintype "passive"))
      (node (ref "CC_X0") (pin "2") (pinfunction "2_2") (pintype "passive"))
      (node (ref "CC_X1") (pin "1") (pinfunction "1_1") (pintype "passive"))
      (node (ref "CC_X1") (pin "2") (pinfunction "2_2") (pintype "passive"))
      (node (ref "CC_X2") (pin "1") (pinfunction "1_1") (pintype "passive"))
      (node (ref "CC_X2") (pin "2") (pinfunction "2_2") (pintype "passive"))
      (node (ref "CC_X4") (pin "1") (pinfunction "1_1") (pintype "passive"))
      (node (ref "CC_X4") (pin "2") (pinfunction "2_2") (pintype "passive"))
      (node (ref "CHPD") (pin "1") (pinfunction "1_1") (pintype "passive"))
      (node (ref "CTX-DB") (pin "1") (pinfunction "S_1") (pintype "passive"))
      (node (ref "DBG") (pin "1") (pinfunction "1_1") (pintype "passive"))
      (node (ref "ESP8266") (pin "VCC") (pinfunction "VCC_VCC") (pintype "bidirectional"))
      (node (ref "HMMOD-UART") (pin "1") (pinfunction "VCC_1") (pintype "power_in"))
      (node (ref "IC2") (pin "10") (pinfunction "V+_10") (pintype "power_in"))
      (node (ref "IC2") (pin "11") (pinfunction "V+_11") (pintype "power_in"))
      (node (ref "NRF24L01+") (pin "2") (pinfunction "VCC_2") (pintype "power_in"))
      (node (ref "U$1") (pin "40") (pinfunction "AV+_40") (pintype "bidirectional"))
      (node (ref "U$2") (pin "VCC") (pinfunction "VCC_VCC") (pintype "bidirectional"))
      (node (ref "UART0") (pin "1") (pinfunction "1_1") (pintype "passive"))
      (node (ref "UART1") (pin "1") (pinfunction "1_1") (pintype "passive"))
    )
    (net (code "61") (name "unconnected-(CC4-PadGDO0)") (class "Default")
      (node (ref "CC4") (pin "GDO0") (pinfunction "GDO0_GDO0") (pintype "bidirectional"))
    )
    (net (code "62") (name "unconnected-(CC_X4-Pad8)") (class "Default")
      (node (ref "CC_X4") (pin "8") (pinfunction "8_8") (pintype "passive"))
    )
    (net (code "63") (name "unconnected-(CTX-DBH-S-Pad7)") (class "Default")
      (node (ref "CTX-DB") (pin "7") (pinfunction "S_7") (pintype "passive"))
    )
    (net (code "64") (name "unconnected-(ESP8266-PadGPIO2)") (class "Default")
      (node (ref "ESP8266") (pin "GPIO2") (pinfunction "GPIO2_GPIO2") (pintype "bidirectional"))
    )
    (net (code "65") (name "unconnected-(ESP8266-PadGPIO12)") (class "Default")
      (node (ref "ESP8266") (pin "GPIO12") (pinfunction "GPIO12_GPIO12") (pintype "bidirectional"))
    )
    (net (code "66") (name "unconnected-(ESP8266-PadGPIO13)") (class "Default")
      (node (ref "ESP8266") (pin "GPIO13") (pinfunction "GPIO13_GPIO13") (pintype "bidirectional"))
    )
    (net (code "67") (name "unconnected-(ESP8266-PadGPIO14)") (class "Default")
      (node (ref "ESP8266") (pin "GPIO14") (pinfunction "GPIO14_GPIO14") (pintype "bidirectional"))
    )
    (net (code "68") (name "unconnected-(ESP8266-PadGPIO18)") (class "Default")
      (node (ref "ESP8266") (pin "GPIO18") (pinfunction "GPIO18_GPIO18") (pintype "bidirectional"))
    )
    (net (code "69") (name "unconnected-(ESP8266-PadNC)") (class "Default")
      (node (ref "ESP8266") (pin "NC") (pinfunction "NC_NC") (pintype "bidirectional"))
    )
    (net (code "70") (name "unconnected-(HMMOD-UART-C2D-Pad3)") (class "Default")
      (node (ref "HMMOD-UART") (pin "3") (pinfunction "C2D_3") (pintype "bidirectional"))
    )
    (net (code "71") (name "unconnected-(HMMOD-UART-\\~{RESET}-Pad4)") (class "Default")
      (node (ref "HMMOD-UART") (pin "4") (pinfunction "\\~{RESET}_4") (pintype "bidirectional"))
    )
    (net (code "72") (name "unconnected-(IC2-NC-Pad9)") (class "Default")
      (node (ref "IC2") (pin "9") (pinfunction "NC_9") (pintype "no_connect"))
    )
    (net (code "73") (name "unconnected-(U$1-23{slash}USB_DP-Pad12)") (class "Default")
      (node (ref "U$1") (pin "12") (pinfunction "23/USB_DP_12") (pintype "bidirectional"))
    )
    (net (code "74") (name "unconnected-(U$1-24{slash}USB_DM-Pad13)") (class "Default")
      (node (ref "U$1") (pin "13") (pinfunction "24/USB_DM_13") (pintype "bidirectional"))
    )
    (net (code "75") (name "unconnected-(U$1-BUT-Pad3)") (class "Default")
      (node (ref "U$1") (pin "3") (pinfunction "BUT_3") (pintype "bidirectional"))
    )
    (net (code "76") (name "unconnected-(U$1-GND-Pad2)") (class "Default")
      (node (ref "U$1") (pin "2") (pinfunction "GND_2") (pintype "bidirectional"))
    )
    (net (code "77") (name "unconnected-(U$1-VBAT-Pad38)") (class "Default")
      (node (ref "U$1") (pin "38") (pinfunction "VBAT_38") (pintype "bidirectional"))
    )
    (net (code "78") (name "unconnected-(U$1-VCC-Pad1)") (class "Default")
      (node (ref "U$1") (pin "1") (pinfunction "VCC_1") (pintype "bidirectional"))
    )
    (net (code "79") (name "unconnected-(U$2-GND1-PadGND4)") (class "Default")
      (node (ref "U$2") (pin "GND4") (pinfunction "GND1_GND4") (pintype "bidirectional"))
    )
    (net (code "80") (name "unconnected-(U$2-GND2-PadGND1)") (class "Default")
      (node (ref "U$2") (pin "GND1") (pinfunction "GND2_GND1") (pintype "bidirectional"))
    )
    (net (code "81") (name "unconnected-(U$2-GND3-PadGND2)") (class "Default")
      (node (ref "U$2") (pin "GND2") (pinfunction "GND3_GND2") (pintype "bidirectional"))
    )
    (net (code "82") (name "unconnected-(U$2-GND4-PadGND3)") (class "Default")
      (node (ref "U$2") (pin "GND3") (pinfunction "GND4_GND3") (pintype "bidirectional"))
    )
    (net (code "83") (name "unconnected-(U$2-PadA0)") (class "Default")
      (node (ref "U$2") (pin "A0") (pinfunction "A0_A0") (pintype "bidirectional"))
    )
    (net (code "84") (name "unconnected-(U$2-PadA1)") (class "Default")
      (node (ref "U$2") (pin "A1") (pinfunction "A1_A1") (pintype "bidirectional"))
    )
    (net (code "85") (name "unconnected-(U$2-PadA2)") (class "Default")
      (node (ref "U$2") (pin "A2") (pinfunction "A2_A2") (pintype "bidirectional"))
    )
    (net (code "86") (name "unconnected-(U$2-PadA3)") (class "Default")
      (node (ref "U$2") (pin "A3") (pinfunction "A3_A3") (pintype "bidirectional"))
    )
    (net (code "87") (name "unconnected-(U$2-PadA4)") (class "Default")
      (node (ref "U$2") (pin "A4") (pinfunction "A4_A4") (pintype "bidirectional"))
    )
    (net (code "88") (name "unconnected-(U$2-PadA5)") (class "Default")
      (node (ref "U$2") (pin "A5") (pinfunction "A5_A5") (pintype "bidirectional"))
    )
    (net (code "89") (name "unconnected-(U$2-PadA6)") (class "Default")
      (node (ref "U$2") (pin "A6") (pinfunction "A6_A6") (pintype "bidirectional"))
    )
    (net (code "90") (name "unconnected-(U$2-PadA7)") (class "Default")
      (node (ref "U$2") (pin "A7") (pinfunction "A7_A7") (pintype "bidirectional"))
    )
    (net (code "91") (name "unconnected-(U$2-PadD3)") (class "Default")
      (node (ref "U$2") (pin "D3") (pinfunction "D3_D3") (pintype "bidirectional"))
    )
    (net (code "92") (name "unconnected-(U$2-PadD4)") (class "Default")
      (node (ref "U$2") (pin "D4") (pinfunction "D4_D4") (pintype "bidirectional"))
    )
    (net (code "93") (name "unconnected-(U$2-PadD5)") (class "Default")
      (node (ref "U$2") (pin "D5") (pinfunction "D5_D5") (pintype "bidirectional"))
    )
    (net (code "94") (name "unconnected-(U$2-PadD6)") (class "Default")
      (node (ref "U$2") (pin "D6") (pinfunction "D6_D6") (pintype "bidirectional"))
    )
    (net (code "95") (name "unconnected-(U$2-PadD7)") (class "Default")
      (node (ref "U$2") (pin "D7") (pinfunction "D7_D7") (pintype "bidirectional"))
    )
    (net (code "96") (name "unconnected-(U$2-PadDTR)") (class "Default")
      (node (ref "U$2") (pin "DTR") (pinfunction "DTR_DTR") (pintype "bidirectional"))
    )
    (net (code "97") (name "unconnected-(U$2-PadRAW)") (class "Default")
      (node (ref "U$2") (pin "RAW") (pinfunction "RAW_RAW") (pintype "bidirectional"))
    )
    (net (code "98") (name "unconnected-(U$2-PadRST)") (class "Default")
      (node (ref "U$2") (pin "RST") (pinfunction "RST_RST") (pintype "bidirectional"))
    )
    (net (code "99") (name "unconnected-(U$2-PadRST1)") (class "Default")
      (node (ref "U$2") (pin "RST1") (pinfunction "RST1_RST1") (pintype "bidirectional"))
    )
    (net (code "100") (name "unconnected-(U$2-PadRX1)") (class "Default")
      (node (ref "U$2") (pin "RX1") (pinfunction "RX1_RX1") (pintype "bidirectional"))
    )
    (net (code "101") (name "unconnected-(U$2-PadTX0)") (class "Default")
      (node (ref "U$2") (pin "TX0") (pinfunction "TX0_TX0") (pintype "bidirectional"))
    )
    (net (code "102") (name "unconnected-(U$2-PadVCC1)") (class "Default")
      (node (ref "U$2") (pin "VCC1") (pinfunction "VCC1_VCC1") (pintype "bidirectional"))
    )
  )
)
